# Fatigue_V1_02.net
KiCad netlist of a schematic drawn in Altium Designer
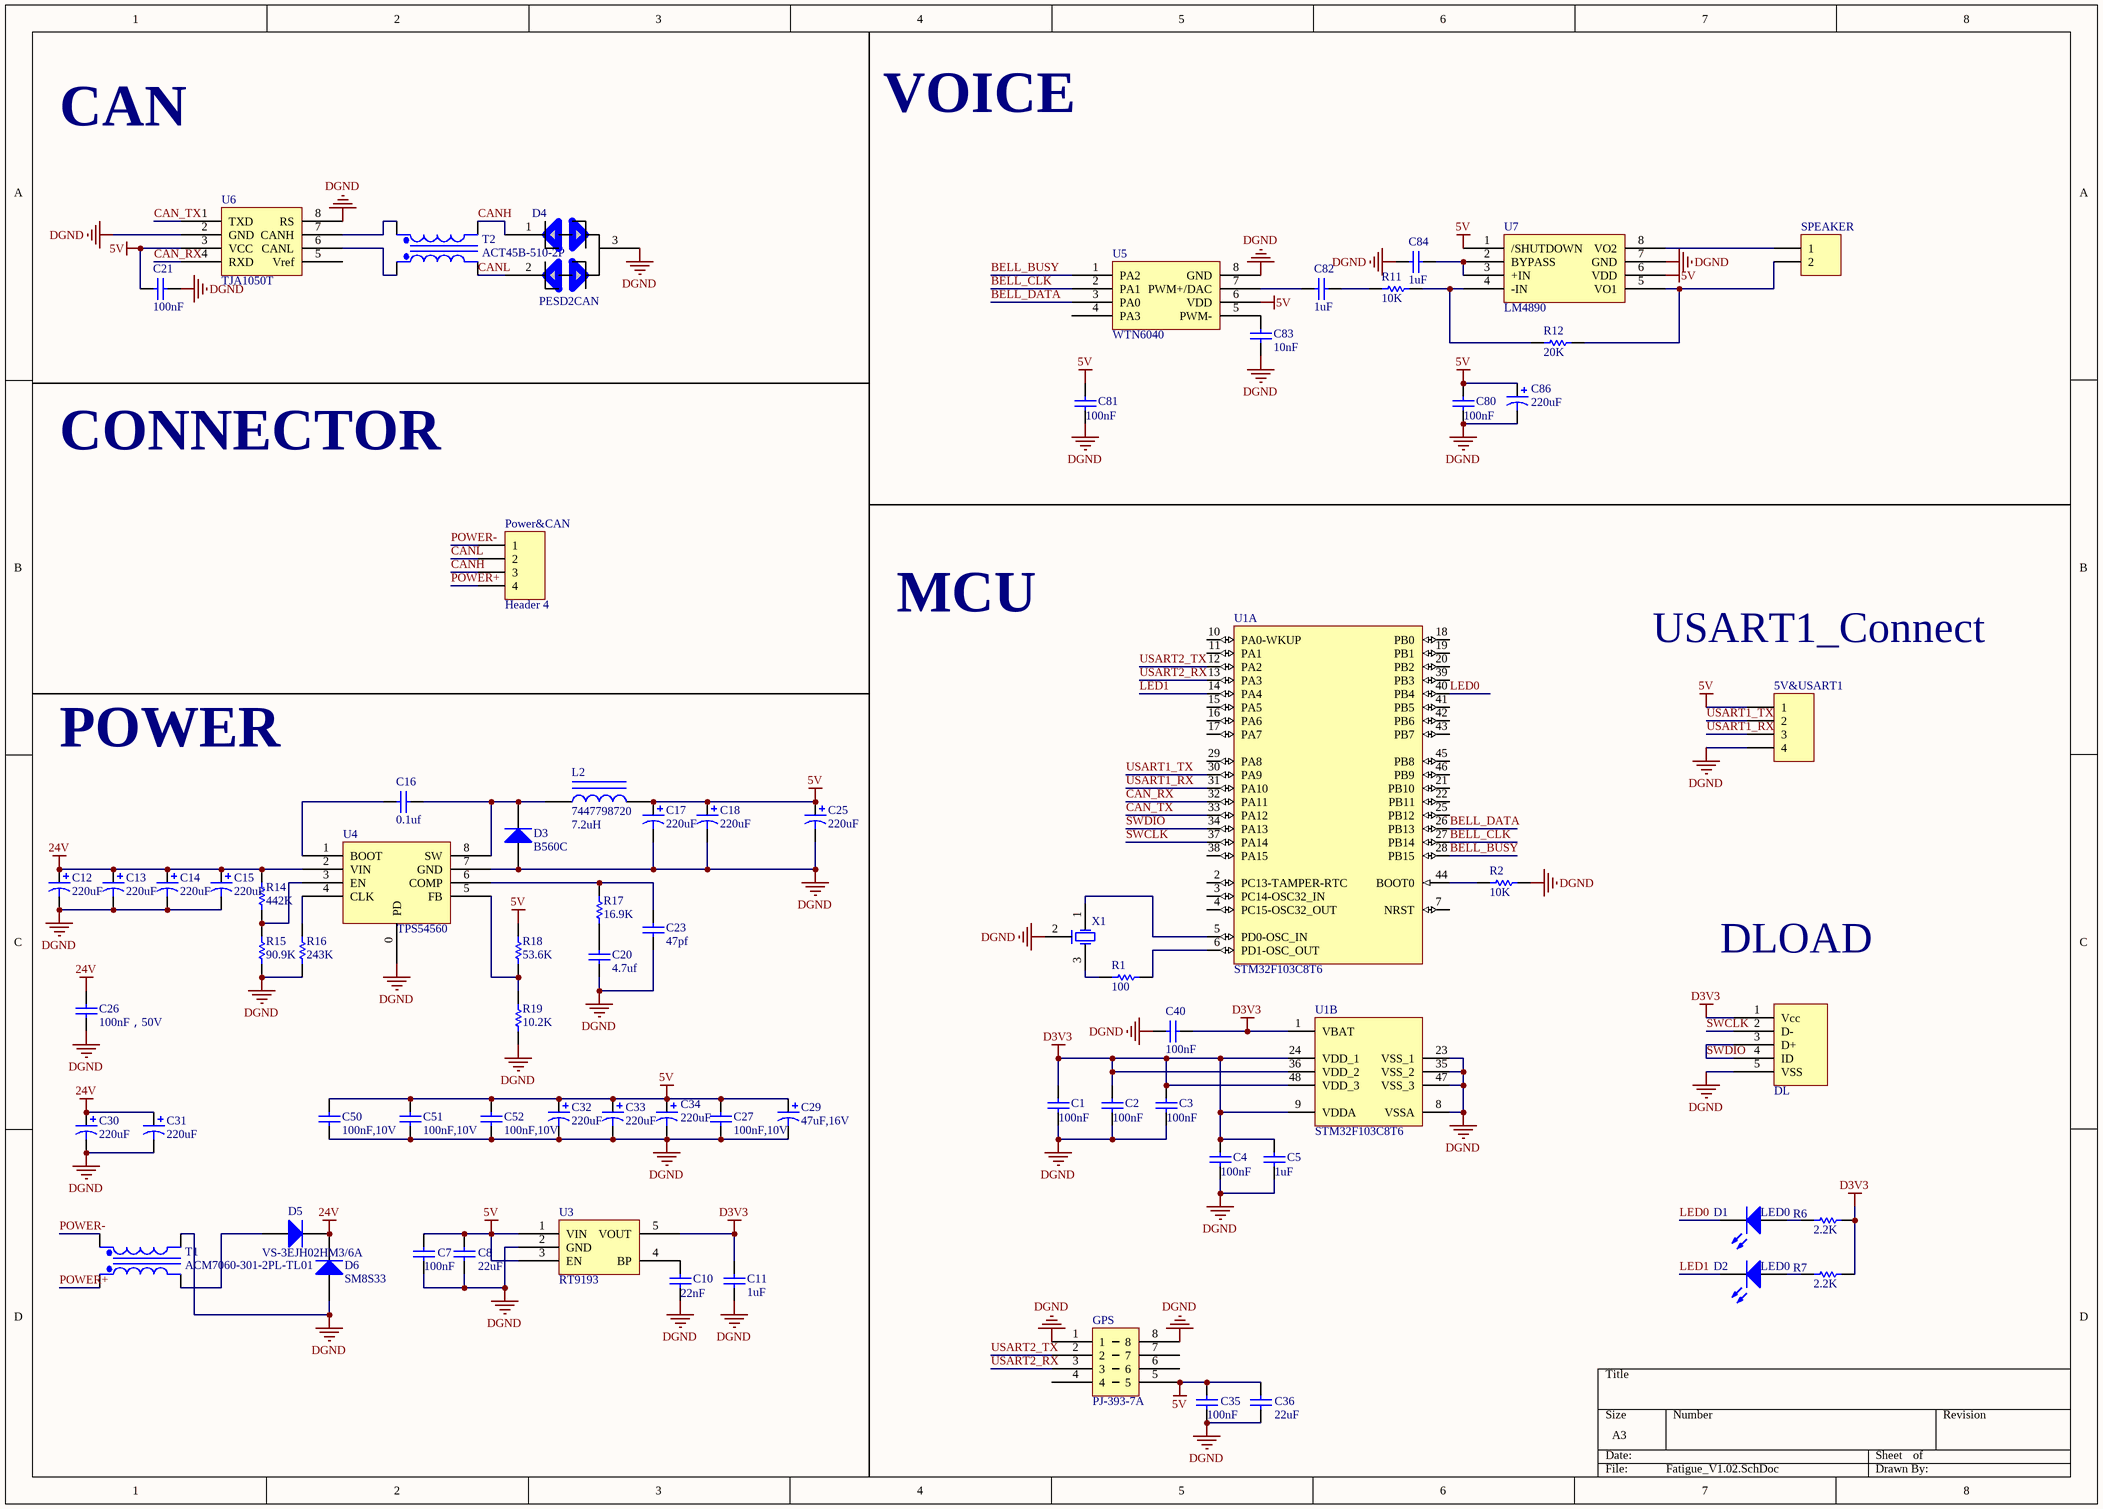
[diagram p0: Fatigue_V1.02.SchDoc]

(export (version "E")
  (design (tool "Eeschema 10.0.6"))
  (components
    (comp (ref "5V&USART1")
      (value "TEST_USART2")
      (footprint "HDR1X4")
      (description "Header, 4-Pin")
      (fields (field (name "PUBLISHER") "Altium Limited"))
      (libsource (lib "Miscellaneous Connectors") (part "Header 4"))
    )
    (comp (ref "C1")
      (value "100nF")
      (footprint "BinFeng:0402")
      (description "Capacitor")
      (fields (field (name "PUBLISHER") "Altium Limited"))
      (libsource (lib "Miscellaneous Devices") (part "Cap"))
    )
    (comp (ref "C2")
      (value "100nF")
      (footprint "BinFeng:0402")
      (description "Capacitor")
      (fields (field (name "PUBLISHER") "Altium Limited"))
      (libsource (lib "Miscellaneous Devices") (part "Cap"))
    )
    (comp (ref "C3")
      (value "100nF")
      (footprint "BinFeng:0402")
      (description "Capacitor")
      (fields (field (name "PUBLISHER") "Altium Limited"))
      (libsource (lib "Miscellaneous Devices") (part "Cap"))
    )
    (comp (ref "C4")
      (value "100nF")
      (footprint "BinFeng:0402")
      (description "Capacitor")
      (fields (field (name "PUBLISHER") "Altium Limited"))
      (libsource (lib "Miscellaneous Devices") (part "Cap"))
    )
    (comp (ref "C5")
      (value "1uF")
      (footprint "BinFeng:0603")
      (description "Capacitor")
      (fields (field (name "PUBLISHER") "Altium Limited"))
      (libsource (lib "Miscellaneous Devices") (part "Cap"))
    )
    (comp (ref "C7")
      (value "100nF")
      (footprint "BinFeng:0402")
      (description "Capacitor,100V")
      (fields (field (name "PUBLISHER") "Altium Limited"))
      (libsource (lib "Miscellaneous Devices") (part "Cap"))
    )
    (comp (ref "C8")
      (value "22uF")
      (footprint "0805")
      (description "Capacitor")
      (fields (field (name "PUBLISHER") "Altium Limited"))
      (libsource (lib "Miscellaneous Devices") (part "Cap"))
    )
    (comp (ref "C10")
      (value "22nF")
      (footprint "BinFeng:0402")
      (description "Capacitor")
      (fields (field (name "PUBLISHER") "Altium Limited"))
      (libsource (lib "Miscellaneous Devices") (part "Cap"))
    )
    (comp (ref "C11")
      (value "1uF")
      (footprint "BinFeng:0603")
      (description "Capacitor")
      (fields (field (name "PUBLISHER") "Altium Limited"))
      (libsource (lib "Miscellaneous Devices") (part "Cap"))
    )
    (comp (ref "C12")
      (value "220uF")
      (footprint "cap_pol_8*10.2")
      (description "Polarized Capacitor (Radial)")
      (fields (field (name "PUBLISHER") "Altium Limited"))
      (libsource (lib "Miscellaneous Devices") (part "Cap Pol1"))
    )
    (comp (ref "C13")
      (value "220uF")
      (footprint "cap_pol_8*10.2")
      (description "Polarized Capacitor (Radial)")
      (fields (field (name "PUBLISHER") "Altium Limited"))
      (libsource (lib "Miscellaneous Devices") (part "Cap Pol1"))
    )
    (comp (ref "C14")
      (value "220uF")
      (footprint "cap_pol_8*10.2")
      (description "Polarized Capacitor (Radial)")
      (fields (field (name "PUBLISHER") "Altium Limited"))
      (libsource (lib "Miscellaneous Devices") (part "Cap Pol1"))
    )
    (comp (ref "C15")
      (value "220uF")
      (footprint "cap_pol_8*10.2")
      (description "Polarized Capacitor (Radial)")
      (fields (field (name "PUBLISHER") "Altium Limited"))
      (libsource (lib "Miscellaneous Devices") (part "Cap Pol1"))
    )
    (comp (ref "C16")
      (value "0.1uf")
      (footprint "0603")
      (description "Capacitor")
      (fields (field (name "PUBLISHER") "Altium Limited"))
      (libsource (lib "Miscellaneous Devices") (part "Cap"))
    )
    (comp (ref "C17")
      (value "220uF")
      (footprint "cap_pol_8*10.2")
      (description "Polarized Capacitor (Radial)")
      (fields (field (name "PUBLISHER") "Altium Limited"))
      (libsource (lib "Miscellaneous Devices") (part "Cap Pol1"))
    )
    (comp (ref "C18")
      (value "220uF")
      (footprint "cap_pol_8*10.2")
      (description "Polarized Capacitor (Radial)")
      (fields (field (name "PUBLISHER") "Altium Limited"))
      (libsource (lib "Miscellaneous Devices") (part "Cap Pol1"))
    )
    (comp (ref "C20")
      (value "4.7uf")
      (footprint "0603")
      (description "Capacitor")
      (fields (field (name "PUBLISHER") "Altium Limited"))
      (libsource (lib "Miscellaneous Devices") (part "Cap"))
    )
    (comp (ref "C21")
      (value "100nF")
      (footprint "BinFeng:0402")
      (description "Capacitor")
      (fields (field (name "PUBLISHER") "Altium Limited"))
      (libsource (lib "Miscellaneous Devices") (part "Cap"))
    )
    (comp (ref "C23")
      (value "47pf")
      (footprint "0603")
      (description "Capacitor")
      (fields (field (name "PUBLISHER") "Altium Limited"))
      (libsource (lib "Miscellaneous Devices") (part "Cap"))
    )
    (comp (ref "C25")
      (value "220uF")
      (footprint "cap_pol_8*10.2")
      (description "Polarized Capacitor (Radial)")
      (fields (field (name "PUBLISHER") "Altium Limited"))
      (libsource (lib "Miscellaneous Devices") (part "Cap Pol1"))
    )
    (comp (ref "C26")
      (value "100nF，50V")
      (footprint "BinFeng:0603")
      (description "Capacitor")
      (fields (field (name "PUBLISHER") "Altium Limited"))
      (libsource (lib "Miscellaneous Devices") (part "Cap"))
    )
    (comp (ref "C27")
      (value "100nF,10V")
      (footprint "BinFeng:0402")
      (description "Capacitor")
      (fields (field (name "PUBLISHER") "Altium Limited"))
      (libsource (lib "Miscellaneous Devices") (part "Cap"))
    )
    (comp (ref "C29")
      (value "47uF,16V")
      (footprint "6032_pol")
      (description "Polarized Capacitor (Radial)")
      (fields (field (name "PUBLISHER") "Altium Limited"))
      (libsource (lib "Miscellaneous Devices") (part "Cap Pol1"))
    )
    (comp (ref "C30")
      (value "220uF")
      (footprint "cap_pol_8*10.2")
      (description "Polarized Capacitor (Radial)")
      (fields (field (name "PUBLISHER") "Altium Limited"))
      (libsource (lib "Miscellaneous Devices") (part "Cap Pol1"))
    )
    (comp (ref "C31")
      (value "220uF")
      (footprint "cap_pol_8*10.2")
      (description "Polarized Capacitor (Radial)")
      (fields (field (name "PUBLISHER") "Altium Limited"))
      (libsource (lib "Miscellaneous Devices") (part "Cap Pol1"))
    )
    (comp (ref "C32")
      (value "220uF")
      (footprint "cap_pol_8*10.2")
      (description "Polarized Capacitor (Radial)")
      (fields (field (name "PUBLISHER") "Altium Limited"))
      (libsource (lib "Miscellaneous Devices") (part "Cap Pol1"))
    )
    (comp (ref "C33")
      (value "220uF")
      (footprint "cap_pol_8*10.2")
      (description "Polarized Capacitor (Radial)")
      (fields (field (name "PUBLISHER") "Altium Limited"))
      (libsource (lib "Miscellaneous Devices") (part "Cap Pol1"))
    )
    (comp (ref "C34")
      (value "220uF")
      (footprint "cap_pol_8*10.2")
      (description "Polarized Capacitor (Radial)")
      (fields (field (name "PUBLISHER") "Altium Limited"))
      (libsource (lib "Miscellaneous Devices") (part "Cap Pol1"))
    )
    (comp (ref "C35")
      (value "100nF")
      (footprint "BinFeng:0402")
      (description "Capacitor,100V")
      (fields (field (name "PUBLISHER") "Altium Limited"))
      (libsource (lib "Miscellaneous Devices") (part "Cap"))
    )
    (comp (ref "C36")
      (value "22uF")
      (footprint "0805")
      (description "Capacitor")
      (fields (field (name "PUBLISHER") "Altium Limited"))
      (libsource (lib "Miscellaneous Devices") (part "Cap"))
    )
    (comp (ref "C40")
      (value "100nF")
      (footprint "BinFeng:0402")
      (description "Capacitor")
      (fields (field (name "PUBLISHER") "Altium Limited"))
      (libsource (lib "Miscellaneous Devices") (part "Cap"))
    )
    (comp (ref "C50")
      (value "100nF,10V")
      (footprint "BinFeng:0402")
      (description "Capacitor")
      (fields (field (name "PUBLISHER") "Altium Limited"))
      (libsource (lib "Miscellaneous Devices") (part "Cap"))
    )
    (comp (ref "C51")
      (value "100nF,10V")
      (footprint "BinFeng:0402")
      (description "Capacitor")
      (fields (field (name "PUBLISHER") "Altium Limited"))
      (libsource (lib "Miscellaneous Devices") (part "Cap"))
    )
    (comp (ref "C52")
      (value "100nF,10V")
      (footprint "BinFeng:0402")
      (description "Capacitor")
      (fields (field (name "PUBLISHER") "Altium Limited"))
      (libsource (lib "Miscellaneous Devices") (part "Cap"))
    )
    (comp (ref "C80")
      (value "100nF")
      (footprint "BinFeng:0402")
      (description "Capacitor")
      (fields (field (name "PUBLISHER") "Altium Limited"))
      (libsource (lib "Miscellaneous Devices") (part "Cap"))
    )
    (comp (ref "C81")
      (value "100nF")
      (footprint "BinFeng:0402")
      (description "Capacitor")
      (fields (field (name "PUBLISHER") "Altium Limited"))
      (libsource (lib "Miscellaneous Devices") (part "Cap"))
    )
    (comp (ref "C82")
      (value "1uF")
      (footprint "BinFeng:0402")
      (description "Capacitor")
      (fields (field (name "PUBLISHER") "Altium Limited"))
      (libsource (lib "Miscellaneous Devices") (part "Cap"))
    )
    (comp (ref "C83")
      (value "10nF")
      (footprint "BinFeng:0402")
      (description "Capacitor")
      (fields (field (name "PUBLISHER") "Altium Limited"))
      (libsource (lib "Miscellaneous Devices") (part "Cap"))
    )
    (comp (ref "C84")
      (value "1uF")
      (footprint "BinFeng:0402")
      (description "Capacitor")
      (fields (field (name "PUBLISHER") "Altium Limited"))
      (libsource (lib "Miscellaneous Devices") (part "Cap"))
    )
    (comp (ref "C86")
      (value "220uF")
      (footprint "cap_pol_8*10.2")
      (description "Polarized Capacitor (Radial)")
      (fields (field (name "PUBLISHER") "Altium Limited"))
      (libsource (lib "Miscellaneous Devices") (part "Cap Pol1"))
    )
    (comp (ref "D1")
      (value "LED0")
      (footprint "1206_LED")
      (description "green LED")
      (fields (field (name "PUBLISHER") "Altium Limited"))
      (libsource (lib "Miscellaneous Devices") (part "LED0"))
    )
    (comp (ref "D2")
      (value "LED0")
      (footprint "1206_LED")
      (description "green LED")
      (fields (field (name "PUBLISHER") "Altium Limited"))
      (libsource (lib "Miscellaneous Devices") (part "LED0"))
    )
    (comp (ref "D3")
      (value "B560C")
      (footprint "BinFeng:SMC")
      (description "1 Amp General Purpose Rectifier")
      (fields (field (name "PUBLISHER") "Altium Limited"))
      (libsource (lib "Miscellaneous Devices") (part "Diode 1N4007"))
    )
    (comp (ref "D4")
      (value "PESD2CAN")
      (footprint "SOT23")
      (libsource (lib "BinFeng_Connectors") (part "PESD1CAN"))
    )
    (comp (ref "D5")
      (value "VS-3EJH02HM3/6A")
      (footprint "back:B290")
      (description "1 Amp General Purpose Rectifier")
      (fields (field (name "PUBLISHER") "Altium Limited"))
      (libsource (lib "Miscellaneous Devices") (part "Diode 1N4007"))
    )
    (comp (ref "D6")
      (value "SM8S33")
      (footprint "SM8S")
      (description "1 Amp General Purpose Rectifier")
      (fields (field (name "PUBLISHER") "Altium Limited"))
      (libsource (lib "Miscellaneous Devices") (part "Diode 1N4007"))
    )
    (comp (ref "DL")
      (value "USB_5pin")
      (footprint "USBmicro_B")
      (libsource (lib "BinFeng_Connectors") (part "USB_5pin"))
    )
    (comp (ref "GPS")
      (value "PJ-393-7A")
      (footprint "3.5mm earphone slot")
      (libsource (lib "BinFeng_IC") (part "3.5mm earphone slot"))
    )
    (comp (ref "L2")
      (value "7447798720")
      (footprint "1064")
      (description "Magnetic-Core Inductor")
      (fields (field (name "ALTIUM_VALUE") "7.2uH") (field (name "PUBLISHER") "Altium Limited"))
      (libsource (lib "Miscellaneous Devices") (part "Inductor Iron"))
    )
    (comp (ref "Power&CAN")
      (value "Header 4")
      (footprint "HDR1X4")
      (description "Header, 4-Pin")
      (fields (field (name "PUBLISHER") "Altium Limited"))
      (libsource (lib "Miscellaneous Connectors") (part "Header 4"))
    )
    (comp (ref "R1")
      (value "100")
      (footprint "BinFeng:0402")
      (description "Resistor")
      (fields (field (name "PUBLISHER") "Altium Limited"))
      (libsource (lib "Miscellaneous Devices") (part "Res1"))
    )
    (comp (ref "R2")
      (value "10K")
      (footprint "BinFeng:0402")
      (description "Resistor")
      (fields (field (name "PUBLISHER") "Altium Limited"))
      (libsource (lib "Miscellaneous Devices") (part "Res1"))
    )
    (comp (ref "R6")
      (value "2.2K")
      (footprint "BinFeng:0402")
      (description "Resistor")
      (fields (field (name "PUBLISHER") "Altium Limited"))
      (libsource (lib "Miscellaneous Devices") (part "Res1"))
    )
    (comp (ref "R7")
      (value "2.2K")
      (footprint "BinFeng:0402")
      (description "Resistor")
      (fields (field (name "PUBLISHER") "Altium Limited"))
      (libsource (lib "Miscellaneous Devices") (part "Res1"))
    )
    (comp (ref "R11")
      (value "10K")
      (footprint "BinFeng:0402")
      (description "Resistor")
      (fields (field (name "PUBLISHER") "Altium Limited"))
      (libsource (lib "Miscellaneous Devices") (part "Res1"))
    )
    (comp (ref "R12")
      (value "20K")
      (footprint "BinFeng:0402")
      (description "Resistor")
      (fields (field (name "PUBLISHER") "Altium Limited"))
      (libsource (lib "Miscellaneous Devices") (part "Res1"))
    )
    (comp (ref "R14")
      (value "442K")
      (footprint "back:0603")
      (description "Resistor")
      (fields (field (name "PUBLISHER") "Altium Limited"))
      (libsource (lib "Miscellaneous Devices") (part "Res1"))
    )
    (comp (ref "R15")
      (value "90.9K")
      (footprint "back:0603")
      (description "Resistor")
      (fields (field (name "PUBLISHER") "Altium Limited"))
      (libsource (lib "Miscellaneous Devices") (part "Res1"))
    )
    (comp (ref "R16")
      (value "243K")
      (footprint "back:0603")
      (description "Resistor")
      (fields (field (name "PUBLISHER") "Altium Limited"))
      (libsource (lib "Miscellaneous Devices") (part "Res1"))
    )
    (comp (ref "R17")
      (value "16.9K")
      (footprint "back:0603")
      (description "Resistor")
      (fields (field (name "PUBLISHER") "Altium Limited"))
      (libsource (lib "Miscellaneous Devices") (part "Res1"))
    )
    (comp (ref "R18")
      (value "53.6K")
      (footprint "back:0603")
      (description "Resistor")
      (fields (field (name "PUBLISHER") "Altium Limited"))
      (libsource (lib "Miscellaneous Devices") (part "Res1"))
    )
    (comp (ref "R19")
      (value "10.2K")
      (footprint "back:0603")
      (description "Resistor")
      (fields (field (name "PUBLISHER") "Altium Limited"))
      (libsource (lib "Miscellaneous Devices") (part "Res1"))
    )
    (comp (ref "SPEAKER")
      (value "SPEAKER")
      (footprint "HDR1X2")
      (description "Header, 2-Pin")
      (fields (field (name "PUBLISHER") "Altium Limited"))
      (libsource (lib "Miscellaneous Connectors") (part "Header 2"))
    )
    (comp (ref "T1")
      (value "ACM7060-301-2PL-TL01")
      (footprint "ACM7060-301-2P-TL01")
      (description "Transformer (Equivalent Circuit Model)")
      (fields (field (name "PUBLISHER") "Altium Limited"))
      (libsource (lib "Miscellaneous Devices") (part "Trans Eq"))
    )
    (comp (ref "T2")
      (value "ACT45B-510-2P")
      (footprint "ACT45B-510-2P")
      (description "Transformer (Equivalent Circuit Model)")
      (fields (field (name "PUBLISHER") "Altium Limited"))
      (libsource (lib "Miscellaneous Devices") (part "Trans Eq"))
    )
    (comp (ref "U1")
      (value "STM32F103C8T6")
      (footprint "STM-LQFP48_N")
      (libsource (lib "STMicroelectronics STM32 F1") (part "STM32F103C8T6"))
    )
    (comp (ref "U3") (value "RT9193") (footprint "SOT-23-5") (libsource (lib "BinFeng_IC") (part "RT9193")))
    (comp (ref "U4") (value "TPS54560") (footprint "HSOIC_8") (libsource (lib "MySchlib1") (part "TPS54560")))
    (comp (ref "U5") (value "WTN6040") (footprint "SO8") (libsource (lib "Schlib3") (part "WTN6040")))
    (comp (ref "U6")
      (value "TJA1050T")
      (footprint "SO8")
      (description "CAN Tranceiver")
      (libsource (lib "BinFeng_IC") (part "TJA1050T"))
    )
    (comp (ref "U7") (value "LM4890") (footprint "MSOP8") (libsource (lib "BinFeng_IC") (part "LM4890")))
    (comp (ref "X1") (value "8M smd") (footprint "8M") (libsource (lib "Schlib1") (part "8M smd")))
  )
  (nets
    (net (code "1") (name "/BELL_BUSY") (class "Default")
      (node (ref "U1") (pin "28") (pinfunction "PB15_28") (pintype "bidirectional"))
      (node (ref "U5") (pin "1") (pinfunction "PA2_1") (pintype "passive"))
    )
    (net (code "2") (name "/BELL_CLK") (class "Default")
      (node (ref "U1") (pin "27") (pinfunction "PB14_27") (pintype "bidirectional"))
      (node (ref "U5") (pin "2") (pinfunction "PA1_2") (pintype "passive"))
    )
    (net (code "3") (name "/BELL_DATA") (class "Default")
      (node (ref "U1") (pin "26") (pinfunction "PB13_26") (pintype "bidirectional"))
      (node (ref "U5") (pin "3") (pinfunction "PA0_3") (pintype "passive"))
    )
    (net (code "4") (name "/CANH") (class "Default")
      (node (ref "D4") (pin "1") (pinfunction "11_1") (pintype "passive"))
      (node (ref "Power&CAN") (pin "3") (pinfunction "3_3") (pintype "passive"))
      (node (ref "T2") (pin "4") (pinfunction "Sec-_4") (pintype "passive"))
    )
    (net (code "5") (name "/CANL") (class "Default")
      (node (ref "D4") (pin "2") (pinfunction "12_2") (pintype "passive"))
      (node (ref "Power&CAN") (pin "2") (pinfunction "2_2") (pintype "passive"))
      (node (ref "T2") (pin "2") (pinfunction "Pri-_2") (pintype "passive"))
    )
    (net (code "6") (name "/CAN_RX") (class "Default")
      (node (ref "U1") (pin "32") (pinfunction "PA11_32") (pintype "bidirectional"))
      (node (ref "U6") (pin "4") (pinfunction "RXD_4") (pintype "passive"))
    )
    (net (code "7") (name "/CAN_TX") (class "Default")
      (node (ref "U1") (pin "33") (pinfunction "PA12_33") (pintype "bidirectional"))
      (node (ref "U6") (pin "1") (pinfunction "TXD_1") (pintype "passive"))
    )
    (net (code "8") (name "/LED0") (class "Default")
      (node (ref "D1") (pin "2") (pinfunction "K_2") (pintype "passive"))
      (node (ref "U1") (pin "40") (pinfunction "PB4_40") (pintype "bidirectional"))
    )
    (net (code "9") (name "/LED1") (class "Default")
      (node (ref "D2") (pin "2") (pinfunction "K_2") (pintype "passive"))
      (node (ref "U1") (pin "14") (pinfunction "PA4_14") (pintype "bidirectional"))
    )
    (net (code "10") (name "/POWER+") (class "Default")
      (node (ref "Power&CAN") (pin "4") (pinfunction "4_4") (pintype "passive"))
      (node (ref "T1") (pin "1") (pinfunction "Pri+_1") (pintype "passive"))
    )
    (net (code "11") (name "/POWER-") (class "Default")
      (node (ref "Power&CAN") (pin "1") (pinfunction "1_1") (pintype "passive"))
      (node (ref "T1") (pin "3") (pinfunction "Sec+_3") (pintype "passive"))
    )
    (net (code "12") (name "/SWCLK") (class "Default")
      (node (ref "DL") (pin "2") (pinfunction "D-_2") (pintype "passive"))
      (node (ref "U1") (pin "37") (pinfunction "PA14_37") (pintype "bidirectional"))
    )
    (net (code "13") (name "/SWDIO") (class "Default")
      (node (ref "DL") (pin "3") (pinfunction "D+_3") (pintype "passive"))
      (node (ref "DL") (pin "4") (pinfunction "ID_4") (pintype "passive"))
      (node (ref "U1") (pin "34") (pinfunction "PA13_34") (pintype "bidirectional"))
    )
    (net (code "14") (name "/USART1_RX") (class "Default")
      (node (ref "5V&USART1") (pin "3") (pinfunction "3_3") (pintype "passive"))
      (node (ref "U1") (pin "31") (pinfunction "PA10_31") (pintype "bidirectional"))
    )
    (net (code "15") (name "/USART1_TX") (class "Default")
      (node (ref "5V&USART1") (pin "2") (pinfunction "2_2") (pintype "passive"))
      (node (ref "U1") (pin "30") (pinfunction "PA9_30") (pintype "bidirectional"))
    )
    (net (code "16") (name "/USART2_RX") (class "Default")
      (node (ref "GPS") (pin "3") (pinfunction "3_3") (pintype "passive"))
      (node (ref "U1") (pin "13") (pinfunction "PA3_13") (pintype "bidirectional"))
    )
    (net (code "17") (name "/USART2_TX") (class "Default")
      (node (ref "GPS") (pin "2") (pinfunction "2_2") (pintype "passive"))
      (node (ref "U1") (pin "12") (pinfunction "PA2_12") (pintype "bidirectional"))
    )
    (net (code "18") (name "5V") (class "Default")
      (node (ref "5V&USART1") (pin "1") (pinfunction "1_1") (pintype "passive"))
      (node (ref "C17") (pin "1") (pinfunction "1_1") (pintype "passive"))
      (node (ref "C18") (pin "1") (pinfunction "1_1") (pintype "passive"))
      (node (ref "C21") (pin "1") (pinfunction "1_1") (pintype "passive"))
      (node (ref "C25") (pin "1") (pinfunction "1_1") (pintype "passive"))
      (node (ref "C27") (pin "1") (pinfunction "1_1") (pintype "passive"))
      (node (ref "C29") (pin "1") (pinfunction "1_1") (pintype "passive"))
      (node (ref "C32") (pin "1") (pinfunction "1_1") (pintype "passive"))
      (node (ref "C33") (pin "1") (pinfunction "1_1") (pintype "passive"))
      (node (ref "C34") (pin "1") (pinfunction "1_1") (pintype "passive"))
      (node (ref "C35") (pin "2") (pinfunction "2_2") (pintype "passive"))
      (node (ref "C36") (pin "2") (pinfunction "2_2") (pintype "passive"))
      (node (ref "C50") (pin "1") (pinfunction "1_1") (pintype "passive"))
      (node (ref "C51") (pin "1") (pinfunction "1_1") (pintype "passive"))
      (node (ref "C52") (pin "1") (pinfunction "1_1") (pintype "passive"))
      (node (ref "C7") (pin "2") (pinfunction "2_2") (pintype "passive"))
      (node (ref "C8") (pin "2") (pinfunction "2_2") (pintype "passive"))
      (node (ref "C80") (pin "2") (pinfunction "2_2") (pintype "passive"))
      (node (ref "C81") (pin "2") (pinfunction "2_2") (pintype "passive"))
      (node (ref "C86") (pin "1") (pinfunction "1_1") (pintype "passive"))
      (node (ref "GPS") (pin "5") (pinfunction "5_5") (pintype "passive"))
      (node (ref "L2") (pin "2") (pinfunction "2_2") (pintype "passive"))
      (node (ref "R18") (pin "2") (pinfunction "2_2") (pintype "passive"))
      (node (ref "U3") (pin "1") (pinfunction "VIN_1") (pintype "passive"))
      (node (ref "U3") (pin "3") (pinfunction "EN_3") (pintype "passive"))
      (node (ref "U5") (pin "6") (pinfunction "VDD_6") (pintype "power_in"))
      (node (ref "U6") (pin "3") (pinfunction "VCC_3") (pintype "passive"))
      (node (ref "U7") (pin "1") (pinfunction "/SHUTDOWN_1") (pintype "passive"))
      (node (ref "U7") (pin "6") (pinfunction "VDD_6") (pintype "passive"))
    )
    (net (code "19") (name "24V") (class "Default")
      (node (ref "C12") (pin "1") (pinfunction "1_1") (pintype "passive"))
      (node (ref "C13") (pin "1") (pinfunction "1_1") (pintype "passive"))
      (node (ref "C14") (pin "1") (pinfunction "1_1") (pintype "passive"))
      (node (ref "C15") (pin "1") (pinfunction "1_1") (pintype "passive"))
      (node (ref "C26") (pin "1") (pinfunction "1_1") (pintype "passive"))
      (node (ref "C30") (pin "1") (pinfunction "1_1") (pintype "passive"))
      (node (ref "C31") (pin "1") (pinfunction "1_1") (pintype "passive"))
      (node (ref "D5") (pin "2") (pinfunction "K_2") (pintype "passive"))
      (node (ref "D6") (pin "2") (pinfunction "K_2") (pintype "passive"))
      (node (ref "R14") (pin "2") (pinfunction "2_2") (pintype "passive"))
      (node (ref "U4") (pin "2") (pinfunction "VIN_2") (pintype "passive"))
    )
    (net (code "20") (name "D3V3") (class "Default")
      (node (ref "C1") (pin "2") (pinfunction "2_2") (pintype "passive"))
      (node (ref "C11") (pin "2") (pinfunction "2_2") (pintype "passive"))
      (node (ref "C2") (pin "2") (pinfunction "2_2") (pintype "passive"))
      (node (ref "C3") (pin "2") (pinfunction "2_2") (pintype "passive"))
      (node (ref "C4") (pin "2") (pinfunction "2_2") (pintype "passive"))
      (node (ref "C40") (pin "1") (pinfunction "1_1") (pintype "passive"))
      (node (ref "C5") (pin "2") (pinfunction "2_2") (pintype "passive"))
      (node (ref "DL") (pin "1") (pinfunction "Vcc_1") (pintype "passive"))
      (node (ref "R6") (pin "1") (pinfunction "1_1") (pintype "passive"))
      (node (ref "R7") (pin "1") (pinfunction "1_1") (pintype "passive"))
      (node (ref "U1") (pin "1") (pinfunction "VBAT_1") (pintype "power_in"))
      (node (ref "U1") (pin "24") (pinfunction "VDD_1_24") (pintype "power_in"))
      (node (ref "U1") (pin "36") (pinfunction "VDD_2_36") (pintype "power_in"))
      (node (ref "U1") (pin "48") (pinfunction "VDD_3_48") (pintype "power_in"))
      (node (ref "U1") (pin "9") (pinfunction "VDDA_9") (pintype "power_in"))
      (node (ref "U3") (pin "5") (pinfunction "VOUT_5") (pintype "passive"))
    )
    (net (code "21") (name "DGND") (class "Default")
      (node (ref "5V&USART1") (pin "4") (pinfunction "4_4") (pintype "passive"))
      (node (ref "C1") (pin "1") (pinfunction "1_1") (pintype "passive"))
      (node (ref "C10") (pin "1") (pinfunction "1_1") (pintype "passive"))
      (node (ref "C11") (pin "1") (pinfunction "1_1") (pintype "passive"))
      (node (ref "C12") (pin "2") (pinfunction "2_2") (pintype "passive"))
      (node (ref "C13") (pin "2") (pinfunction "2_2") (pintype "passive"))
      (node (ref "C14") (pin "2") (pinfunction "2_2") (pintype "passive"))
      (node (ref "C15") (pin "2") (pinfunction "2_2") (pintype "passive"))
      (node (ref "C17") (pin "2") (pinfunction "2_2") (pintype "passive"))
      (node (ref "C18") (pin "2") (pinfunction "2_2") (pintype "passive"))
      (node (ref "C2") (pin "1") (pinfunction "1_1") (pintype "passive"))
      (node (ref "C20") (pin "2") (pinfunction "2_2") (pintype "passive"))
      (node (ref "C21") (pin "2") (pinfunction "2_2") (pintype "passive"))
      (node (ref "C23") (pin "2") (pinfunction "2_2") (pintype "passive"))
      (node (ref "C25") (pin "2") (pinfunction "2_2") (pintype "passive"))
      (node (ref "C26") (pin "2") (pinfunction "2_2") (pintype "passive"))
      (node (ref "C27") (pin "2") (pinfunction "2_2") (pintype "passive"))
      (node (ref "C29") (pin "2") (pinfunction "2_2") (pintype "passive"))
      (node (ref "C3") (pin "1") (pinfunction "1_1") (pintype "passive"))
      (node (ref "C30") (pin "2") (pinfunction "2_2") (pintype "passive"))
      (node (ref "C31") (pin "2") (pinfunction "2_2") (pintype "passive"))
      (node (ref "C32") (pin "2") (pinfunction "2_2") (pintype "passive"))
      (node (ref "C33") (pin "2") (pinfunction "2_2") (pintype "passive"))
      (node (ref "C34") (pin "2") (pinfunction "2_2") (pintype "passive"))
      (node (ref "C35") (pin "1") (pinfunction "1_1") (pintype "passive"))
      (node (ref "C36") (pin "1") (pinfunction "1_1") (pintype "passive"))
      (node (ref "C4") (pin "1") (pinfunction "1_1") (pintype "passive"))
      (node (ref "C40") (pin "2") (pinfunction "2_2") (pintype "passive"))
      (node (ref "C5") (pin "1") (pinfunction "1_1") (pintype "passive"))
      (node (ref "C50") (pin "2") (pinfunction "2_2") (pintype "passive"))
      (node (ref "C51") (pin "2") (pinfunction "2_2") (pintype "passive"))
      (node (ref "C52") (pin "2") (pinfunction "2_2") (pintype "passive"))
      (node (ref "C7") (pin "1") (pinfunction "1_1") (pintype "passive"))
      (node (ref "C8") (pin "1") (pinfunction "1_1") (pintype "passive"))
      (node (ref "C80") (pin "1") (pinfunction "1_1") (pintype "passive"))
      (node (ref "C81") (pin "1") (pinfunction "1_1") (pintype "passive"))
      (node (ref "C83") (pin "2") (pinfunction "2_2") (pintype "passive"))
      (node (ref "C84") (pin "2") (pinfunction "2_2") (pintype "passive"))
      (node (ref "C86") (pin "2") (pinfunction "2_2") (pintype "passive"))
      (node (ref "D3") (pin "1") (pinfunction "A_1") (pintype "passive"))
      (node (ref "D4") (pin "3") (pinfunction "13_3") (pintype "passive"))
      (node (ref "D6") (pin "1") (pinfunction "A_1") (pintype "passive"))
      (node (ref "DL") (pin "5") (pinfunction "VSS_5") (pintype "passive"))
      (node (ref "GPS") (pin "1") (pinfunction "1_1") (pintype "passive"))
      (node (ref "GPS") (pin "8") (pinfunction "8_8") (pintype "passive"))
      (node (ref "R15") (pin "1") (pinfunction "1_1") (pintype "passive"))
      (node (ref "R16") (pin "1") (pinfunction "1_1") (pintype "passive"))
      (node (ref "R19") (pin "1") (pinfunction "1_1") (pintype "passive"))
      (node (ref "R2") (pin "2") (pinfunction "2_2") (pintype "passive"))
      (node (ref "T1") (pin "4") (pinfunction "Sec-_4") (pintype "passive"))
      (node (ref "U1") (pin "23") (pinfunction "VSS_1_23") (pintype "power_in"))
      (node (ref "U1") (pin "35") (pinfunction "VSS_2_35") (pintype "power_in"))
      (node (ref "U1") (pin "47") (pinfunction "VSS_3_47") (pintype "power_in"))
      (node (ref "U1") (pin "8") (pinfunction "VSSA_8") (pintype "power_in"))
      (node (ref "U3") (pin "2") (pinfunction "GND_2") (pintype "passive"))
      (node (ref "U4") (pin "0") (pinfunction "PD_0") (pintype "passive"))
      (node (ref "U4") (pin "7") (pinfunction "GND_7") (pintype "passive"))
      (node (ref "U5") (pin "8") (pinfunction "GND_8") (pintype "power_in"))
      (node (ref "U6") (pin "2") (pinfunction "GND_2") (pintype "passive"))
      (node (ref "U6") (pin "8") (pinfunction "RS_8") (pintype "passive"))
      (node (ref "U7") (pin "7") (pinfunction "GND_7") (pintype "passive"))
      (node (ref "X1") (pin "2") (pinfunction "GND_2") (pintype "passive"))
    )
    (net (code "22") (name "Net-(C20-Pad1)") (class "Default")
      (node (ref "C20") (pin "1") (pinfunction "1_1") (pintype "passive"))
      (node (ref "R17") (pin "1") (pinfunction "1_1") (pintype "passive"))
    )
    (net (code "23") (name "Net-(C82-Pad1)") (class "Default")
      (node (ref "C82") (pin "1") (pinfunction "1_1") (pintype "passive"))
      (node (ref "R11") (pin "1") (pinfunction "1_1") (pintype "passive"))
    )
    (net (code "24") (name "Net-(D1-A)") (class "Default")
      (node (ref "D1") (pin "1") (pinfunction "A_1") (pintype "passive"))
      (node (ref "R6") (pin "2") (pinfunction "2_2") (pintype "passive"))
    )
    (net (code "25") (name "Net-(D2-A)") (class "Default")
      (node (ref "D2") (pin "1") (pinfunction "A_1") (pintype "passive"))
      (node (ref "R7") (pin "2") (pinfunction "2_2") (pintype "passive"))
    )
    (net (code "26") (name "Net-(D3-K)") (class "Default")
      (node (ref "C16") (pin "1") (pinfunction "1_1") (pintype "passive"))
      (node (ref "D3") (pin "2") (pinfunction "K_2") (pintype "passive"))
      (node (ref "L2") (pin "1") (pinfunction "1_1") (pintype "passive"))
      (node (ref "U4") (pin "8") (pinfunction "SW_8") (pintype "passive"))
    )
    (net (code "27") (name "Net-(D5-A)") (class "Default")
      (node (ref "D5") (pin "1") (pinfunction "A_1") (pintype "passive"))
      (node (ref "T1") (pin "2") (pinfunction "Pri-_2") (pintype "passive"))
    )
    (net (code "28") (name "Net-(T2-Pri+)") (class "Default")
      (node (ref "T2") (pin "1") (pinfunction "Pri+_1") (pintype "passive"))
      (node (ref "U6") (pin "6") (pinfunction "CANL_6") (pintype "passive"))
    )
    (net (code "29") (name "Net-(T2-Sec+)") (class "Default")
      (node (ref "T2") (pin "3") (pinfunction "Sec+_3") (pintype "passive"))
      (node (ref "U6") (pin "7") (pinfunction "CANH_7") (pintype "passive"))
    )
    (net (code "30") (name "Net-(U1A-BOOT0)") (class "Default")
      (node (ref "R2") (pin "1") (pinfunction "1_1") (pintype "passive"))
      (node (ref "U1") (pin "44") (pinfunction "BOOT0_44") (pintype "input"))
    )
    (net (code "31") (name "Net-(U1A-PD0-OSC_IN)") (class "Default")
      (node (ref "U1") (pin "5") (pinfunction "PD0-OSC_IN_5") (pintype "bidirectional"))
      (node (ref "X1") (pin "1") (pinfunction "OSC1_1") (pintype "passive"))
    )
    (net (code "32") (name "Net-(U1A-PD1-OSC_OUT)") (class "Default")
      (node (ref "R1") (pin "2") (pinfunction "2_2") (pintype "passive"))
      (node (ref "U1") (pin "6") (pinfunction "PD1-OSC_OUT_6") (pintype "bidirectional"))
    )
    (net (code "33") (name "Net-(U3-BP)") (class "Default")
      (node (ref "C10") (pin "2") (pinfunction "2_2") (pintype "passive"))
      (node (ref "U3") (pin "4") (pinfunction "BP_4") (pintype "passive"))
    )
    (net (code "34") (name "Net-(U4-BOOT)") (class "Default")
      (node (ref "C16") (pin "2") (pinfunction "2_2") (pintype "passive"))
      (node (ref "U4") (pin "1") (pinfunction "BOOT_1") (pintype "passive"))
    )
    (net (code "35") (name "Net-(U4-CLK)") (class "Default")
      (node (ref "R16") (pin "2") (pinfunction "2_2") (pintype "passive"))
      (node (ref "U4") (pin "4") (pinfunction "CLK_4") (pintype "passive"))
    )
    (net (code "36") (name "Net-(U4-COMP)") (class "Default")
      (node (ref "C23") (pin "1") (pinfunction "1_1") (pintype "passive"))
      (node (ref "R17") (pin "2") (pinfunction "2_2") (pintype "passive"))
      (node (ref "U4") (pin "6") (pinfunction "COMP_6") (pintype "passive"))
    )
    (net (code "37") (name "Net-(U4-EN)") (class "Default")
      (node (ref "R14") (pin "1") (pinfunction "1_1") (pintype "passive"))
      (node (ref "R15") (pin "2") (pinfunction "2_2") (pintype "passive"))
      (node (ref "U4") (pin "3") (pinfunction "EN_3") (pintype "passive"))
    )
    (net (code "38") (name "Net-(U4-FB)") (class "Default")
      (node (ref "R18") (pin "1") (pinfunction "1_1") (pintype "passive"))
      (node (ref "R19") (pin "2") (pinfunction "2_2") (pintype "passive"))
      (node (ref "U4") (pin "5") (pinfunction "FB_5") (pintype "passive"))
    )
    (net (code "39") (name "Net-(U5-PWM+{slash}DAC)") (class "Default")
      (node (ref "C82") (pin "2") (pinfunction "2_2") (pintype "passive"))
      (node (ref "U5") (pin "7") (pinfunction "PWM+/DAC_7") (pintype "passive"))
    )
    (net (code "40") (name "Net-(U5-PWM-)") (class "Default")
      (node (ref "C83") (pin "1") (pinfunction "1_1") (pintype "passive"))
      (node (ref "U5") (pin "5") (pinfunction "PWM-_5") (pintype "passive"))
    )
    (net (code "41") (name "Net-(U7-+IN)") (class "Default")
      (node (ref "C84") (pin "1") (pinfunction "1_1") (pintype "passive"))
      (node (ref "U7") (pin "2") (pinfunction "BYPASS_2") (pintype "passive"))
      (node (ref "U7") (pin "3") (pinfunction "+IN_3") (pintype "passive"))
    )
    (net (code "42") (name "Net-(U7--IN)") (class "Default")
      (node (ref "R11") (pin "2") (pinfunction "2_2") (pintype "passive"))
      (node (ref "R12") (pin "1") (pinfunction "1_1") (pintype "passive"))
      (node (ref "U7") (pin "4") (pinfunction "-IN_4") (pintype "passive"))
    )
    (net (code "43") (name "Net-(U7-VO1)") (class "Default")
      (node (ref "R12") (pin "2") (pinfunction "2_2") (pintype "passive"))
      (node (ref "SPEAKER") (pin "2") (pinfunction "2_2") (pintype "passive"))
      (node (ref "U7") (pin "5") (pinfunction "VO1_5") (pintype "passive"))
    )
    (net (code "44") (name "Net-(U7-VO2)") (class "Default")
      (node (ref "SPEAKER") (pin "1") (pinfunction "1_1") (pintype "passive"))
      (node (ref "U7") (pin "8") (pinfunction "VO2_8") (pintype "passive"))
    )
    (net (code "45") (name "Net-(X1-OSC2)") (class "Default")
      (node (ref "R1") (pin "1") (pinfunction "1_1") (pintype "passive"))
      (node (ref "X1") (pin "3") (pinfunction "OSC2_3") (pintype "passive"))
    )
    (net (code "46") (name "unconnected-(GPS-Pad4)") (class "Default")
      (node (ref "GPS") (pin "4") (pinfunction "4_4") (pintype "passive"))
    )
    (net (code "47") (name "unconnected-(GPS-Pad6)") (class "Default")
      (node (ref "GPS") (pin "6") (pinfunction "6_6") (pintype "passive"))
    )
    (net (code "48") (name "unconnected-(GPS-Pad7)") (class "Default")
      (node (ref "GPS") (pin "7") (pinfunction "7_7") (pintype "passive"))
    )
    (net (code "49") (name "unconnected-(U1A-NRST-Pad7)") (class "Default")
      (node (ref "U1") (pin "7") (pinfunction "NRST_7") (pintype "bidirectional"))
    )
    (net (code "50") (name "unconnected-(U1A-PA0-WKUP-Pad10)") (class "Default")
      (node (ref "U1") (pin "10") (pinfunction "PA0-WKUP_10") (pintype "bidirectional"))
    )
    (net (code "51") (name "unconnected-(U1A-PA1-Pad11)") (class "Default")
      (node (ref "U1") (pin "11") (pinfunction "PA1_11") (pintype "bidirectional"))
    )
    (net (code "52") (name "unconnected-(U1A-PA5-Pad15)") (class "Default")
      (node (ref "U1") (pin "15") (pinfunction "PA5_15") (pintype "bidirectional"))
    )
    (net (code "53") (name "unconnected-(U1A-PA6-Pad16)") (class "Default")
      (node (ref "U1") (pin "16") (pinfunction "PA6_16") (pintype "bidirectional"))
    )
    (net (code "54") (name "unconnected-(U1A-PA7-Pad17)") (class "Default")
      (node (ref "U1") (pin "17") (pinfunction "PA7_17") (pintype "bidirectional"))
    )
    (net (code "55") (name "unconnected-(U1A-PA8-Pad29)") (class "Default")
      (node (ref "U1") (pin "29") (pinfunction "PA8_29") (pintype "bidirectional"))
    )
    (net (code "56") (name "unconnected-(U1A-PA15-Pad38)") (class "Default")
      (node (ref "U1") (pin "38") (pinfunction "PA15_38") (pintype "bidirectional"))
    )
    (net (code "57") (name "unconnected-(U1A-PB0-Pad18)") (class "Default")
      (node (ref "U1") (pin "18") (pinfunction "PB0_18") (pintype "bidirectional"))
    )
    (net (code "58") (name "unconnected-(U1A-PB1-Pad19)") (class "Default")
      (node (ref "U1") (pin "19") (pinfunction "PB1_19") (pintype "bidirectional"))
    )
    (net (code "59") (name "unconnected-(U1A-PB2-Pad20)") (class "Default")
      (node (ref "U1") (pin "20") (pinfunction "PB2_20") (pintype "bidirectional"))
    )
    (net (code "60") (name "unconnected-(U1A-PB3-Pad39)") (class "Default")
      (node (ref "U1") (pin "39") (pinfunction "PB3_39") (pintype "bidirectional"))
    )
    (net (code "61") (name "unconnected-(U1A-PB5-Pad41)") (class "Default")
      (node (ref "U1") (pin "41") (pinfunction "PB5_41") (pintype "bidirectional"))
    )
    (net (code "62") (name "unconnected-(U1A-PB6-Pad42)") (class "Default")
      (node (ref "U1") (pin "42") (pinfunction "PB6_42") (pintype "bidirectional"))
    )
    (net (code "63") (name "unconnected-(U1A-PB7-Pad43)") (class "Default")
      (node (ref "U1") (pin "43") (pinfunction "PB7_43") (pintype "bidirectional"))
    )
    (net (code "64") (name "unconnected-(U1A-PB8-Pad45)") (class "Default")
      (node (ref "U1") (pin "45") (pinfunction "PB8_45") (pintype "bidirectional"))
    )
    (net (code "65") (name "unconnected-(U1A-PB9-Pad46)") (class "Default")
      (node (ref "U1") (pin "46") (pinfunction "PB9_46") (pintype "bidirectional"))
    )
    (net (code "66") (name "unconnected-(U1A-PB10-Pad21)") (class "Default")
      (node (ref "U1") (pin "21") (pinfunction "PB10_21") (pintype "bidirectional"))
    )
    (net (code "67") (name "unconnected-(U1A-PB11-Pad22)") (class "Default")
      (node (ref "U1") (pin "22") (pinfunction "PB11_22") (pintype "bidirectional"))
    )
    (net (code "68") (name "unconnected-(U1A-PB12-Pad25)") (class "Default")
      (node (ref "U1") (pin "25") (pinfunction "PB12_25") (pintype "bidirectional"))
    )
    (net (code "69") (name "unconnected-(U1A-PC13-TAMPER-RTC-Pad2)") (class "Default")
      (node (ref "U1") (pin "2") (pinfunction "PC13-TAMPER-RTC_2") (pintype "bidirectional"))
    )
    (net (code "70") (name "unconnected-(U1A-PC14-OSC32_IN-Pad3)") (class "Default")
      (node (ref "U1") (pin "3") (pinfunction "PC14-OSC32_IN_3") (pintype "bidirectional"))
    )
    (net (code "71") (name "unconnected-(U1A-PC15-OSC32_OUT-Pad4)") (class "Default")
      (node (ref "U1") (pin "4") (pinfunction "PC15-OSC32_OUT_4") (pintype "bidirectional"))
    )
    (net (code "72") (name "unconnected-(U5-PA3-Pad4)") (class "Default")
      (node (ref "U5") (pin "4") (pinfunction "PA3_4") (pintype "passive"))
    )
    (net (code "73") (name "unconnected-(U6-Vref-Pad5)") (class "Default")
      (node (ref "U6") (pin "5") (pinfunction "Vref_5") (pintype "passive"))
    )
  )
)
